# ttl2rs232.net
KiCad netlist of a schematic drawn in EAGLE
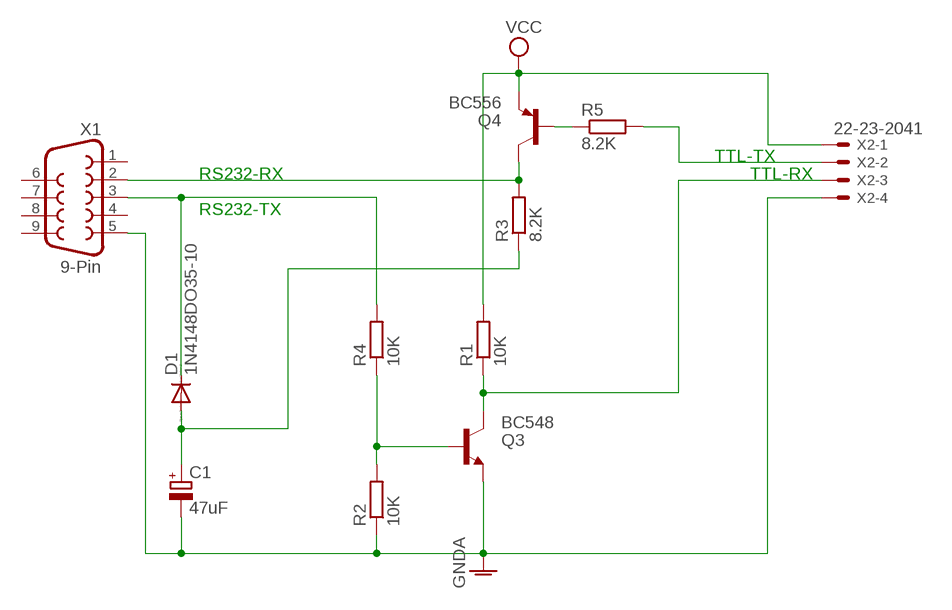
[diagram p0: schematic, sheet 1]

(export (version "E")
  (design (tool "Eeschema 10.0.6"))
  (components
    (comp (ref "C1")
      (value "47uF")
      (footprint "eagle-import:E2,5-7")
      (libsource (lib "eagle-import") (part "CPOL-EUE2.5-7"))
    )
    (comp (ref "D1")
      (value "1N4148DO35-10")
      (footprint "eagle-import:DO35-10")
      (libsource (lib "eagle-import") (part "1N4148DO35-10"))
    )
    (comp (ref "Q3")
      (value "BC548")
      (footprint "eagle-import:TO92-EBC")
      (libsource (lib "eagle-import") (part "BC548"))
    )
    (comp (ref "Q4")
      (value "BC556")
      (footprint "eagle-import:TO92-EBC")
      (libsource (lib "eagle-import") (part "BC556"))
    )
    (comp (ref "R1")
      (value "10K")
      (footprint "eagle-import:0207_10")
      (libsource (lib "eagle-import") (part "R-EU_0207/10"))
    )
    (comp (ref "R2")
      (value "10K")
      (footprint "eagle-import:0207_10")
      (libsource (lib "eagle-import") (part "R-EU_0207/10"))
    )
    (comp (ref "R3")
      (value "8.2K")
      (footprint "eagle-import:0207_10")
      (libsource (lib "eagle-import") (part "R-EU_0207/10"))
    )
    (comp (ref "R4")
      (value "10K")
      (footprint "eagle-import:0207_10")
      (libsource (lib "eagle-import") (part "R-EU_0207/10"))
    )
    (comp (ref "R5")
      (value "8.2K")
      (footprint "eagle-import:0207_10")
      (libsource (lib "eagle-import") (part "R-EU_0207/10"))
    )
    (comp (ref "X1")
      (value "9-Pin")
      (footprint "eagle-import:F09H")
      (libsource (lib "eagle-import") (part "F09H"))
    )
    (comp (ref "X2")
      (value "22-23-2041")
      (footprint "eagle-import:22-23-2041")
      (fields (field (name "MF") "MOLEX"))
      (libsource (lib "eagle-import") (part "22-23-2041"))
    )
  )
  (nets
    (net (code "1") (name "GNDA") (class "Default")
      (node (ref "C1") (pin "-") (pinfunction "-_-") (pintype "passive"))
      (node (ref "Q3") (pin "E") (pinfunction "E_E") (pintype "passive"))
      (node (ref "R2") (pin "1") (pinfunction "1_1") (pintype "passive"))
      (node (ref "X1") (pin "5") (pinfunction "5_5") (pintype "passive"))
      (node (ref "X2") (pin "4") (pinfunction "S_4") (pintype "passive"))
    )
    (net (code "2") (name "Net-(C1-Pad+)") (class "Default")
      (node (ref "C1") (pin "+") (pinfunction "+_+") (pintype "passive"))
      (node (ref "D1") (pin "A") (pinfunction "A_A") (pintype "passive"))
      (node (ref "R3") (pin "1") (pinfunction "1_1") (pintype "passive"))
    )
    (net (code "3") (name "Net-(D1-PadC)") (class "Default")
      (node (ref "D1") (pin "C") (pinfunction "C_C") (pintype "passive"))
      (node (ref "R4") (pin "2") (pinfunction "2_2") (pintype "passive"))
      (node (ref "X1") (pin "3") (pinfunction "3_3") (pintype "passive"))
    )
    (net (code "4") (name "Net-(Q3-PadB)") (class "Default")
      (node (ref "Q3") (pin "B") (pinfunction "B_B") (pintype "passive"))
      (node (ref "R2") (pin "2") (pinfunction "2_2") (pintype "passive"))
      (node (ref "R4") (pin "1") (pinfunction "1_1") (pintype "passive"))
    )
    (net (code "5") (name "Net-(Q4-PadB)") (class "Default")
      (node (ref "Q4") (pin "B") (pinfunction "B_B") (pintype "passive"))
      (node (ref "R5") (pin "1") (pinfunction "1_1") (pintype "passive"))
    )
    (net (code "6") (name "Net-(Q4-PadC)") (class "Default")
      (node (ref "Q4") (pin "C") (pinfunction "C_C") (pintype "passive"))
      (node (ref "R3") (pin "2") (pinfunction "2_2") (pintype "passive"))
      (node (ref "X1") (pin "2") (pinfunction "2_2") (pintype "passive"))
    )
    (net (code "7") (name "Net-(X2B-S)") (class "Default")
      (node (ref "R5") (pin "2") (pinfunction "2_2") (pintype "passive"))
      (node (ref "X2") (pin "2") (pinfunction "S_2") (pintype "passive"))
    )
    (net (code "8") (name "Net-(X2C-S)") (class "Default")
      (node (ref "Q3") (pin "C") (pinfunction "C_C") (pintype "passive"))
      (node (ref "R1") (pin "1") (pinfunction "1_1") (pintype "passive"))
      (node (ref "X2") (pin "3") (pinfunction "S_3") (pintype "passive"))
    )
    (net (code "9") (name "VCC") (class "Default")
      (node (ref "Q4") (pin "E") (pinfunction "E_E") (pintype "passive"))
      (node (ref "R1") (pin "2") (pinfunction "2_2") (pintype "passive"))
      (node (ref "X2") (pin "1") (pinfunction "S_1") (pintype "passive"))
    )
    (net (code "10") (name "unconnected-(X1-Pad1)") (class "Default")
      (node (ref "X1") (pin "1") (pinfunction "1_1") (pintype "passive"))
    )
    (net (code "11") (name "unconnected-(X1-Pad4)") (class "Default")
      (node (ref "X1") (pin "4") (pinfunction "4_4") (pintype "passive"))
    )
    (net (code "12") (name "unconnected-(X1-Pad6)") (class "Default")
      (node (ref "X1") (pin "6") (pinfunction "6_6") (pintype "passive"))
    )
    (net (code "13") (name "unconnected-(X1-Pad7)") (class "Default")
      (node (ref "X1") (pin "7") (pinfunction "7_7") (pintype "passive"))
    )
    (net (code "14") (name "unconnected-(X1-Pad8)") (class "Default")
      (node (ref "X1") (pin "8") (pinfunction "8_8") (pintype "passive"))
    )
    (net (code "15") (name "unconnected-(X1-Pad9)") (class "Default")
      (node (ref "X1") (pin "9") (pinfunction "9_9") (pintype "passive"))
    )
  )
)
